# 15_Clocks_2.net
KiCad netlist of a schematic drawn in Altium Designer
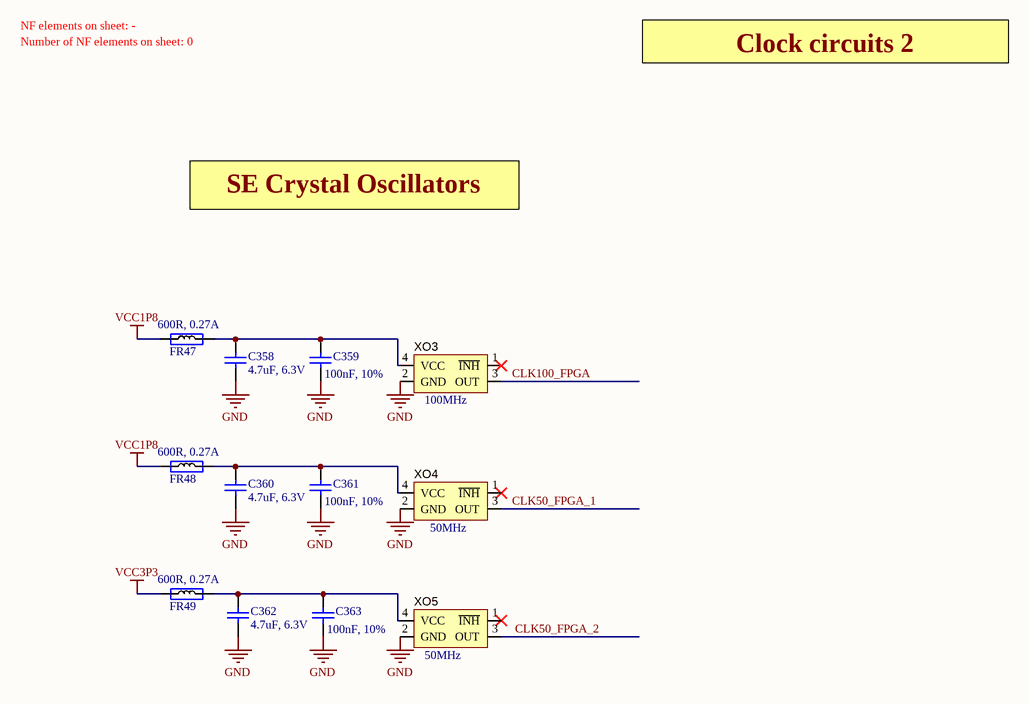
[diagram p0: 15_Clocks_2.SchDoc]

(export (version "E")
  (design (tool "Eeschema 10.0.6"))
  (components
    (comp (ref "C358")
      (value "4.7uF, 6.3V")
      (footprint "CAP0402")
      (fields
        (field (name "MANUFACTURER") "Murata Electronics North America")
        (field (name "TOLERANCE") "±20%")
      )
      (libsource (lib "LimeMicroAltiumLib_schLib") (part "Cap_0402"))
    )
    (comp (ref "C359")
      (value "100nF, 10%")
      (footprint "CAP0402")
      (fields
        (field (name "TOLERANCE") "10 %")
        (field (name "MANUFACTURER") "Murata Electronics")
        (field (name "MANUFACTURER PART NUMBER") "GRM155R71C104KA88D")
      )
      (libsource (lib "LimeFPGAboard_schLib") (part "Cap_0603"))
    )
    (comp (ref "C360")
      (value "4.7uF, 6.3V")
      (footprint "CAP0402")
      (fields
        (field (name "MANUFACTURER") "Murata Electronics North America")
        (field (name "TOLERANCE") "±20%")
      )
      (libsource (lib "LimeMicroAltiumLib_schLib") (part "Cap_0402"))
    )
    (comp (ref "C361")
      (value "100nF, 10%")
      (footprint "CAP0402")
      (fields
        (field (name "TOLERANCE") "10 %")
        (field (name "MANUFACTURER") "Murata Electronics")
        (field (name "MANUFACTURER PART NUMBER") "GRM155R71C104KA88D")
      )
      (libsource (lib "LimeFPGAboard_schLib") (part "Cap_0603"))
    )
    (comp (ref "C362")
      (value "4.7uF, 6.3V")
      (footprint "CAP0402")
      (fields
        (field (name "MANUFACTURER") "Murata Electronics North America")
        (field (name "TOLERANCE") "±20%")
      )
      (libsource (lib "LimeMicroAltiumLib_schLib") (part "Cap_0402"))
    )
    (comp (ref "C363")
      (value "100nF, 10%")
      (footprint "CAP0402")
      (fields
        (field (name "TOLERANCE") "10 %")
        (field (name "MANUFACTURER") "Murata Electronics")
        (field (name "MANUFACTURER PART NUMBER") "GRM155R71C104KA88D")
      )
      (libsource (lib "LimeFPGAboard_schLib") (part "Cap_0603"))
    )
    (comp (ref "FR47")
      (value "600R, 0.27A")
      (footprint "RES0201")
      (fields (field (name "MANUFACTURER") "Taiyo Yuden"))
      (libsource (lib "LimeMicroAltiumLib_schLib") (part "Ferrite"))
    )
    (comp (ref "FR48")
      (value "600R, 0.27A")
      (footprint "RES0201")
      (fields (field (name "MANUFACTURER") "Taiyo Yuden"))
      (libsource (lib "LimeMicroAltiumLib_schLib") (part "Ferrite"))
    )
    (comp (ref "FR49")
      (value "600R, 0.27A")
      (footprint "RES0201")
      (fields (field (name "MANUFACTURER") "Taiyo Yuden"))
      (libsource (lib "LimeMicroAltiumLib_schLib") (part "Ferrite"))
    )
    (comp (ref "XO3")
      (value "100MHz")
      (footprint "CRYSTAL_4-LCC_v4")
      (description "Oscillator Crystal")
      (fields
        (field (name "MANUFACTURER PART NUMBER") "KC5032A100.000C1GE00")
        (field (name "MANUFACTURER") "AVX Corp/Kyocera Corp")
      )
      (libsource (lib "LimeMicroAltiumLib_schLib") (part "CRYSTAL"))
    )
    (comp (ref "XO4")
      (value "50MHz")
      (footprint "CRYSTAL_4-LCC_v4")
      (description "Oscillator Crystal")
      (fields
        (field (name "MANUFACTURER PART NUMBER") "KC5032A50.0000CMGE00")
        (field (name "MANUFACTURER") "AVX Corp/Kyocera Corp")
      )
      (libsource (lib "LimeMicroAltiumLib_schLib") (part "CRYSTAL"))
    )
    (comp (ref "XO5")
      (value "50MHz")
      (footprint "CRYSTAL_4-LCC_v4")
      (description "Oscillator Crystal")
      (fields
        (field (name "MANUFACTURER PART NUMBER") "KC5032A50.0000CMGE00")
        (field (name "MANUFACTURER") "AVX Corp/Kyocera Corp")
      )
      (libsource (lib "LimeMicroAltiumLib_schLib") (part "CRYSTAL"))
    )
  )
  (nets
    (net (code "1") (name "/CLK50_FPGA_1") (class "Default")
      (node (ref "XO4") (pin "3") (pinfunction "OUT_3") (pintype "passive"))
    )
    (net (code "2") (name "/CLK50_FPGA_2") (class "Default")
      (node (ref "XO5") (pin "3") (pinfunction "OUT_3") (pintype "passive"))
    )
    (net (code "3") (name "/CLK100_FPGA") (class "Default")
      (node (ref "XO3") (pin "3") (pinfunction "OUT_3") (pintype "passive"))
    )
    (net (code "4") (name "GND") (class "Default")
      (node (ref "C358") (pin "1") (pinfunction "1_1") (pintype "passive"))
      (node (ref "C359") (pin "2") (pinfunction "2_2") (pintype "passive"))
      (node (ref "C360") (pin "1") (pinfunction "1_1") (pintype "passive"))
      (node (ref "C361") (pin "2") (pinfunction "2_2") (pintype "passive"))
      (node (ref "C362") (pin "1") (pinfunction "1_1") (pintype "passive"))
      (node (ref "C363") (pin "2") (pinfunction "2_2") (pintype "passive"))
      (node (ref "XO3") (pin "2") (pinfunction "GND_2") (pintype "passive"))
      (node (ref "XO4") (pin "2") (pinfunction "GND_2") (pintype "passive"))
      (node (ref "XO5") (pin "2") (pinfunction "GND_2") (pintype "passive"))
    )
    (net (code "5") (name "Net-(XO3-VCC)") (class "Default")
      (node (ref "C358") (pin "2") (pinfunction "2_2") (pintype "passive"))
      (node (ref "C359") (pin "1") (pinfunction "1_1") (pintype "passive"))
      (node (ref "FR47") (pin "2") (pinfunction "2_2") (pintype "passive"))
      (node (ref "XO3") (pin "4") (pinfunction "VCC_4") (pintype "passive"))
    )
    (net (code "6") (name "Net-(XO4-VCC)") (class "Default")
      (node (ref "C360") (pin "2") (pinfunction "2_2") (pintype "passive"))
      (node (ref "C361") (pin "1") (pinfunction "1_1") (pintype "passive"))
      (node (ref "FR48") (pin "2") (pinfunction "2_2") (pintype "passive"))
      (node (ref "XO4") (pin "4") (pinfunction "VCC_4") (pintype "passive"))
    )
    (net (code "7") (name "Net-(XO5-VCC)") (class "Default")
      (node (ref "C362") (pin "2") (pinfunction "2_2") (pintype "passive"))
      (node (ref "C363") (pin "1") (pinfunction "1_1") (pintype "passive"))
      (node (ref "FR49") (pin "2") (pinfunction "2_2") (pintype "passive"))
      (node (ref "XO5") (pin "4") (pinfunction "VCC_4") (pintype "passive"))
    )
    (net (code "8") (name "VCC1P8") (class "Default")
      (node (ref "FR47") (pin "1") (pinfunction "1_1") (pintype "passive"))
      (node (ref "FR48") (pin "1") (pinfunction "1_1") (pintype "passive"))
    )
    (net (code "9") (name "VCC3P3") (class "Default")
      (node (ref "FR49") (pin "1") (pinfunction "1_1") (pintype "passive"))
    )
    (net (code "10") (name "unconnected-(XO3-~{INH}-Pad1)") (class "Default")
      (node (ref "XO3") (pin "1") (pinfunction "~{INH}_1") (pintype "passive+no_connect"))
    )
    (net (code "11") (name "unconnected-(XO4-~{INH}-Pad1)") (class "Default")
      (node (ref "XO4") (pin "1") (pinfunction "~{INH}_1") (pintype "passive+no_connect"))
    )
    (net (code "12") (name "unconnected-(XO5-~{INH}-Pad1)") (class "Default")
      (node (ref "XO5") (pin "1") (pinfunction "~{INH}_1") (pintype "passive+no_connect"))
    )
  )
)
